# Gamebadge3_revD.net
KiCad netlist of a schematic drawn in EAGLE
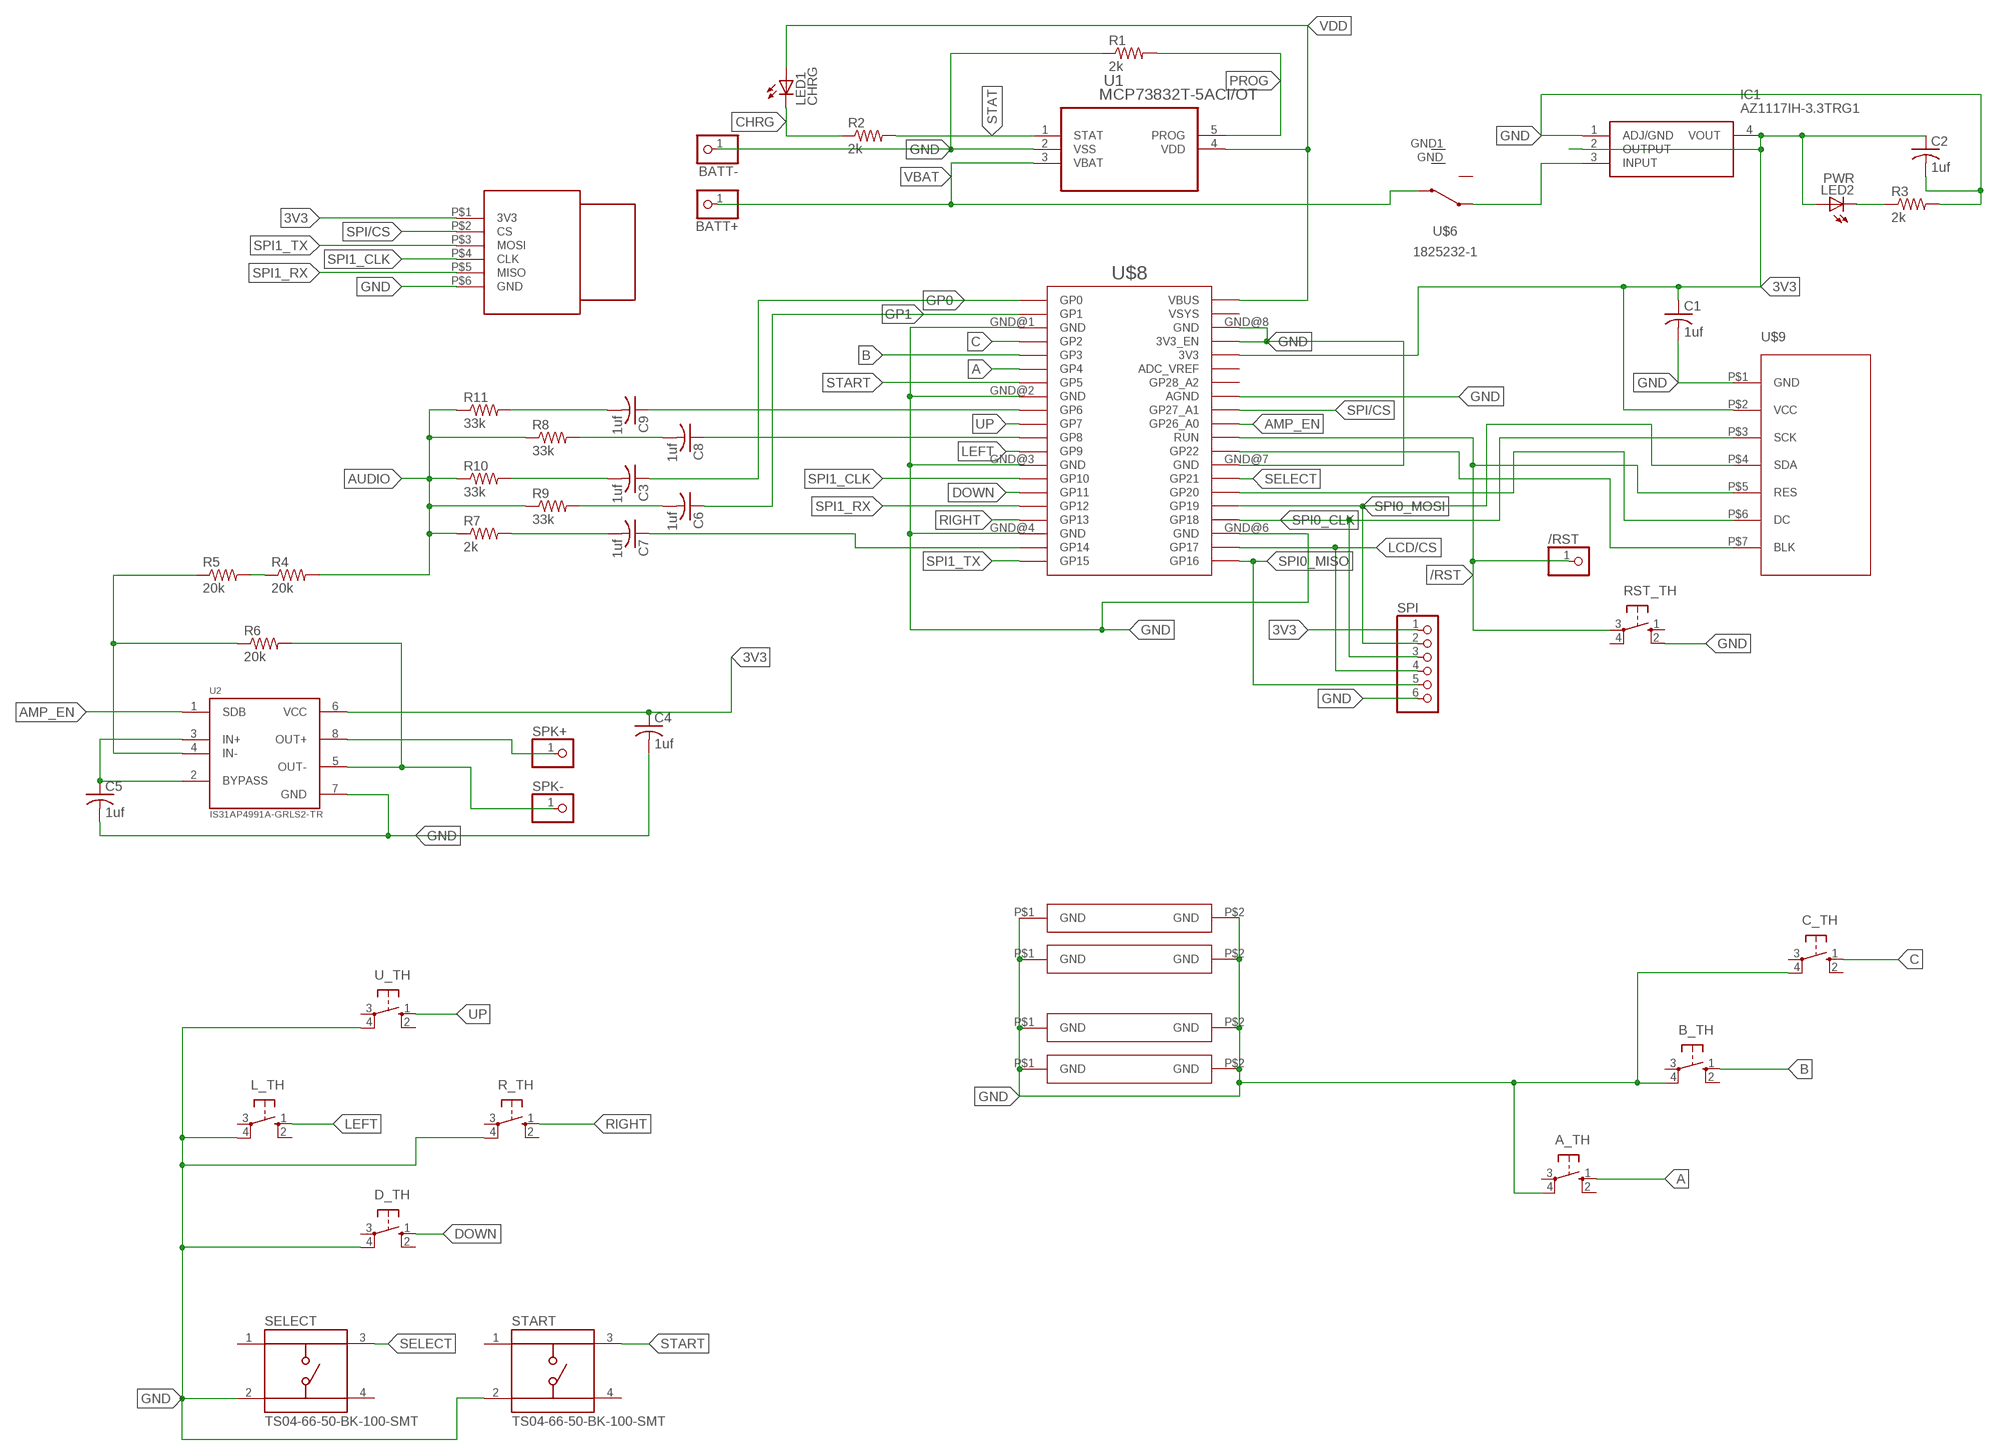
[diagram p0: schematic, sheet 1]

(export (version "E")
  (design (tool "Eeschema 10.0.6"))
  (components
    (comp (ref "/RST")
      (value "PINHD-1X1")
      (footprint "eagle-import:1X01")
      (libsource (lib "eagle-import") (part "PINHD-1X1"))
    )
    (comp (ref "A_TH")
      (value "10-XX")
      (footprint "eagle-import:B3F-10XX")
      (fields (field (name "MPN") "B3F-1000"))
      (libsource (lib "eagle-import") (part "10-XX"))
    )
    (comp (ref "BATT+")
      (value "PINHD-1X1")
      (footprint "eagle-import:1X01")
      (libsource (lib "eagle-import") (part "PINHD-1X1"))
    )
    (comp (ref "BATT-")
      (value "PINHD-1X1")
      (footprint "eagle-import:1X01")
      (libsource (lib "eagle-import") (part "PINHD-1X1"))
    )
    (comp (ref "B_TH")
      (value "10-XX")
      (footprint "eagle-import:B3F-10XX")
      (fields (field (name "MPN") "B3F-1000"))
      (libsource (lib "eagle-import") (part "10-XX"))
    )
    (comp (ref "C1")
      (value "1uf")
      (footprint "eagle-import:C0805")
      (libsource (lib "eagle-import") (part "C-USC0805"))
    )
    (comp (ref "C2")
      (value "1uf")
      (footprint "eagle-import:C0805")
      (libsource (lib "eagle-import") (part "C-USC0805"))
    )
    (comp (ref "C3")
      (value "1uf")
      (footprint "eagle-import:C0805")
      (libsource (lib "eagle-import") (part "C-USC0805"))
    )
    (comp (ref "C4")
      (value "1uf")
      (footprint "eagle-import:C0805")
      (libsource (lib "eagle-import") (part "C-USC0805"))
    )
    (comp (ref "C5")
      (value "1uf")
      (footprint "eagle-import:C0805")
      (libsource (lib "eagle-import") (part "C-USC0805"))
    )
    (comp (ref "C6")
      (value "1uf")
      (footprint "eagle-import:C0805")
      (libsource (lib "eagle-import") (part "C-USC0805"))
    )
    (comp (ref "C7")
      (value "1uf")
      (footprint "eagle-import:C0805")
      (libsource (lib "eagle-import") (part "C-USC0805"))
    )
    (comp (ref "C8")
      (value "1uf")
      (footprint "eagle-import:C0805")
      (libsource (lib "eagle-import") (part "C-USC0805"))
    )
    (comp (ref "C9")
      (value "1uf")
      (footprint "eagle-import:C0805")
      (libsource (lib "eagle-import") (part "C-USC0805"))
    )
    (comp (ref "C_TH")
      (value "10-XX")
      (footprint "eagle-import:B3F-10XX")
      (fields (field (name "MPN") "B3F-1000"))
      (libsource (lib "eagle-import") (part "10-XX"))
    )
    (comp (ref "D_TH")
      (value "10-XX")
      (footprint "eagle-import:B3F-10XX")
      (fields (field (name "MPN") "B3F-1000"))
      (libsource (lib "eagle-import") (part "10-XX"))
    )
    (comp (ref "IC1")
      (value "AZ1117IH-3.3TRG1")
      (footprint "eagle-import:SOT230P700X170-4N")
      (fields (field (name "MF") "Diodes Inc."))
      (libsource (lib "eagle-import") (part "AZ1117IH-3.3TRG1"))
    )
    (comp (ref "LED1")
      (value "CHRG")
      (footprint "eagle-import:LED3MM")
      (libsource (lib "eagle-import") (part "LED3MM"))
    )
    (comp (ref "LED2")
      (value "PWR")
      (footprint "eagle-import:LED3MM")
      (libsource (lib "eagle-import") (part "LED3MM"))
    )
    (comp (ref "L_TH")
      (value "10-XX")
      (footprint "eagle-import:B3F-10XX")
      (fields (field (name "MPN") "B3F-1000"))
      (libsource (lib "eagle-import") (part "10-XX"))
    )
    (comp (ref "R1")
      (value "2k")
      (footprint "eagle-import:R0805")
      (libsource (lib "eagle-import") (part "R-US_R0805"))
    )
    (comp (ref "R2")
      (value "2k")
      (footprint "eagle-import:R0805")
      (libsource (lib "eagle-import") (part "R-US_R0805"))
    )
    (comp (ref "R3")
      (value "2k")
      (footprint "eagle-import:R0805")
      (libsource (lib "eagle-import") (part "R-US_R0805"))
    )
    (comp (ref "R4")
      (value "20k")
      (footprint "eagle-import:R0805")
      (libsource (lib "eagle-import") (part "R-US_R0805"))
    )
    (comp (ref "R5")
      (value "20k")
      (footprint "eagle-import:R0805")
      (libsource (lib "eagle-import") (part "R-US_R0805"))
    )
    (comp (ref "R6")
      (value "20k")
      (footprint "eagle-import:R0805")
      (libsource (lib "eagle-import") (part "R-US_R0805"))
    )
    (comp (ref "R7")
      (value "2k")
      (footprint "eagle-import:R0805")
      (libsource (lib "eagle-import") (part "R-US_R0805"))
    )
    (comp (ref "R8")
      (value "33k")
      (footprint "eagle-import:R0805")
      (libsource (lib "eagle-import") (part "R-US_R0805"))
    )
    (comp (ref "R9")
      (value "33k")
      (footprint "eagle-import:R0805")
      (libsource (lib "eagle-import") (part "R-US_R0805"))
    )
    (comp (ref "R10")
      (value "33k")
      (footprint "eagle-import:R0805")
      (libsource (lib "eagle-import") (part "R-US_R0805"))
    )
    (comp (ref "R11")
      (value "33k")
      (footprint "eagle-import:R0805")
      (libsource (lib "eagle-import") (part "R-US_R0805"))
    )
    (comp (ref "RST_TH")
      (value "10-XX")
      (footprint "eagle-import:B3F-10XX")
      (fields (field (name "MPN") "B3F-1000"))
      (libsource (lib "eagle-import") (part "10-XX"))
    )
    (comp (ref "R_TH")
      (value "10-XX")
      (footprint "eagle-import:B3F-10XX")
      (fields (field (name "MPN") "B3F-1000"))
      (libsource (lib "eagle-import") (part "10-XX"))
    )
    (comp (ref "SELECT")
      (value "TS04-66-50-BK-100-SMT")
      (footprint "eagle-import:SW_TS04-66-50-BK-100-SMT")
      (fields (field (name "MF") "CUI Devices"))
      (libsource (lib "eagle-import") (part "TS04-66-50-BK-100-SMT"))
    )
    (comp (ref "SPI")
      (value "PINHD-1X6")
      (footprint "eagle-import:1X06")
      (libsource (lib "eagle-import") (part "PINHD-1X6"))
    )
    (comp (ref "SPK+")
      (value "PINHD-1X1")
      (footprint "eagle-import:1X01")
      (libsource (lib "eagle-import") (part "PINHD-1X1"))
    )
    (comp (ref "SPK-")
      (value "PINHD-1X1")
      (footprint "eagle-import:1X01")
      (libsource (lib "eagle-import") (part "PINHD-1X1"))
    )
    (comp (ref "START")
      (value "TS04-66-50-BK-100-SMT")
      (footprint "eagle-import:SW_TS04-66-50-BK-100-SMT")
      (fields (field (name "MF") "CUI Devices"))
      (libsource (lib "eagle-import") (part "TS04-66-50-BK-100-SMT"))
    )
    (comp (ref "U$1")
      (value "SD_CARD_ADAPTER")
      (footprint "eagle-import:SD_CARD")
      (libsource (lib "eagle-import") (part "SD_CARD_ADAPTER"))
    )
    (comp (ref "U$2")
      (value "GND_CLIP")
      (footprint "eagle-import:GND_CLIP")
      (libsource (lib "eagle-import") (part "GND_CLIP"))
    )
    (comp (ref "U$3")
      (value "GND_CLIP")
      (footprint "eagle-import:GND_CLIP")
      (libsource (lib "eagle-import") (part "GND_CLIP"))
    )
    (comp (ref "U$4")
      (value "GND_CLIP")
      (footprint "eagle-import:GND_CLIP")
      (libsource (lib "eagle-import") (part "GND_CLIP"))
    )
    (comp (ref "U$5")
      (value "GND_CLIP")
      (footprint "eagle-import:GND_CLIP")
      (libsource (lib "eagle-import") (part "GND_CLIP"))
    )
    (comp (ref "U$6")
      (value "1825232-1")
      (footprint "eagle-import:1825232-1")
      (fields (field (name "MF") "TE Connectivity"))
      (libsource (lib "eagle-import") (part "1825232-1"))
    )
    (comp (ref "U$8")
      (value "RPI_PICO_W")
      (footprint "eagle-import:RPI_PICO_W")
      (libsource (lib "eagle-import") (part "RPI_PICO_W"))
    )
    (comp (ref "U$9")
      (value "ST7789")
      (footprint "eagle-import:ST7789")
      (libsource (lib "eagle-import") (part "ST7789"))
    )
    (comp (ref "U1")
      (value "MCP73832T-5ACI/OT")
      (footprint "eagle-import:SOT95P300X145-5N")
      (fields (field (name "MF") "Microchip"))
      (libsource (lib "eagle-import") (part "MCP73832T-5ACI/OT"))
    )
    (comp (ref "U2")
      (value "IS31AP4991A-GRLS2-TR")
      (footprint "eagle-import:SOIC127P604X170-8N")
      (fields (field (name "MF") "Lumissil Microsystems"))
      (libsource (lib "eagle-import") (part "IS31AP4991A-GRLS2-TR"))
    )
    (comp (ref "U_TH")
      (value "10-XX")
      (footprint "eagle-import:B3F-10XX")
      (fields (field (name "MPN") "B3F-1000"))
      (libsource (lib "eagle-import") (part "10-XX"))
    )
  )
  (nets
    (net (code "1") (name "3V3") (class "Default")
      (node (ref "C1") (pin "1") (pinfunction "1_1") (pintype "passive"))
      (node (ref "C2") (pin "1") (pinfunction "1_1") (pintype "passive"))
      (node (ref "C4") (pin "1") (pinfunction "1_1") (pintype "passive"))
      (node (ref "IC1") (pin "2") (pinfunction "OUTPUT_2") (pintype "bidirectional"))
      (node (ref "IC1") (pin "4") (pinfunction "VOUT_4") (pintype "bidirectional"))
      (node (ref "LED2") (pin "A") (pinfunction "A_A") (pintype "passive"))
      (node (ref "SPI") (pin "1") (pinfunction "1_1") (pintype "passive"))
      (node (ref "U$1") (pin "P$1") (pinfunction "3V3_P$1") (pintype "bidirectional"))
      (node (ref "U$8") (pin "3V3") (pinfunction "3V3_3V3") (pintype "bidirectional"))
      (node (ref "U$9") (pin "P$2") (pinfunction "VCC_P$2") (pintype "bidirectional"))
      (node (ref "U2") (pin "6") (pinfunction "VCC_6") (pintype "power_in"))
    )
    (net (code "2") (name "A") (class "Default")
      (node (ref "A_TH") (pin "1") (pinfunction "S_1") (pintype "passive"))
      (node (ref "U$8") (pin "GP4") (pinfunction "GP4_GP4") (pintype "bidirectional"))
    )
    (net (code "3") (name "AMP_EN") (class "Default")
      (node (ref "U$8") (pin "GP26_A0") (pinfunction "GP26_A0_GP26_A0") (pintype "bidirectional"))
      (node (ref "U2") (pin "1") (pinfunction "SDB_1") (pintype "input"))
    )
    (net (code "4") (name "AUDIO") (class "Default")
      (node (ref "R10") (pin "1") (pinfunction "1_1") (pintype "passive"))
      (node (ref "R11") (pin "1") (pinfunction "1_1") (pintype "passive"))
      (node (ref "R4") (pin "2") (pinfunction "2_2") (pintype "passive"))
      (node (ref "R7") (pin "1") (pinfunction "1_1") (pintype "passive"))
      (node (ref "R8") (pin "1") (pinfunction "1_1") (pintype "passive"))
      (node (ref "R9") (pin "1") (pinfunction "1_1") (pintype "passive"))
    )
    (net (code "5") (name "B") (class "Default")
      (node (ref "B_TH") (pin "1") (pinfunction "S_1") (pintype "passive"))
      (node (ref "U$8") (pin "GP3") (pinfunction "GP3_GP3") (pintype "bidirectional"))
    )
    (net (code "6") (name "C") (class "Default")
      (node (ref "C_TH") (pin "1") (pinfunction "S_1") (pintype "passive"))
      (node (ref "U$8") (pin "GP2") (pinfunction "GP2_GP2") (pintype "bidirectional"))
    )
    (net (code "7") (name "CHRG") (class "Default")
      (node (ref "LED1") (pin "K") (pinfunction "C_K") (pintype "passive"))
      (node (ref "R2") (pin "1") (pinfunction "1_1") (pintype "passive"))
    )
    (net (code "8") (name "DOWN") (class "Default")
      (node (ref "D_TH") (pin "1") (pinfunction "S_1") (pintype "passive"))
      (node (ref "U$8") (pin "GP11") (pinfunction "GP11_GP11") (pintype "bidirectional"))
    )
    (net (code "9") (name "GND") (class "Default")
      (node (ref "A_TH") (pin "4") (pinfunction "P1_4") (pintype "passive"))
      (node (ref "BATT-") (pin "1") (pinfunction "1_1") (pintype "passive"))
      (node (ref "B_TH") (pin "4") (pinfunction "P1_4") (pintype "passive"))
      (node (ref "C1") (pin "2") (pinfunction "2_2") (pintype "passive"))
      (node (ref "C2") (pin "2") (pinfunction "2_2") (pintype "passive"))
      (node (ref "C4") (pin "2") (pinfunction "2_2") (pintype "passive"))
      (node (ref "C5") (pin "2") (pinfunction "2_2") (pintype "passive"))
      (node (ref "C_TH") (pin "4") (pinfunction "P1_4") (pintype "passive"))
      (node (ref "D_TH") (pin "4") (pinfunction "P1_4") (pintype "passive"))
      (node (ref "IC1") (pin "1") (pinfunction "ADJ/GND_1") (pintype "bidirectional"))
      (node (ref "L_TH") (pin "4") (pinfunction "P1_4") (pintype "passive"))
      (node (ref "R1") (pin "1") (pinfunction "1_1") (pintype "passive"))
      (node (ref "R3") (pin "2") (pinfunction "2_2") (pintype "passive"))
      (node (ref "RST_TH") (pin "2") (pinfunction "S1_2") (pintype "passive"))
      (node (ref "R_TH") (pin "4") (pinfunction "P1_4") (pintype "passive"))
      (node (ref "SELECT") (pin "2") (pinfunction "2_2") (pintype "passive"))
      (node (ref "SPI") (pin "6") (pinfunction "6_6") (pintype "passive"))
      (node (ref "START") (pin "2") (pinfunction "2_2") (pintype "passive"))
      (node (ref "U$1") (pin "P$6") (pinfunction "GND_P$6") (pintype "bidirectional"))
      (node (ref "U$2") (pin "P$1") (pinfunction "GND_P$1") (pintype "bidirectional"))
      (node (ref "U$2") (pin "P$2") (pinfunction "GND_P$2") (pintype "bidirectional"))
      (node (ref "U$3") (pin "P$1") (pinfunction "GND_P$1") (pintype "bidirectional"))
      (node (ref "U$3") (pin "P$2") (pinfunction "GND_P$2") (pintype "bidirectional"))
      (node (ref "U$4") (pin "P$1") (pinfunction "GND_P$1") (pintype "bidirectional"))
      (node (ref "U$4") (pin "P$2") (pinfunction "GND_P$2") (pintype "bidirectional"))
      (node (ref "U$5") (pin "P$1") (pinfunction "GND_P$1") (pintype "bidirectional"))
      (node (ref "U$5") (pin "P$2") (pinfunction "GND_P$2") (pintype "bidirectional"))
      (node (ref "U$8") (pin "3V3_EN") (pinfunction "3V3_EN_3V3_EN") (pintype "bidirectional"))
      (node (ref "U$8") (pin "AGND") (pinfunction "AGND_AGND") (pintype "bidirectional"))
      (node (ref "U$8") (pin "GND@1") (pinfunction "GND_GND@1") (pintype "bidirectional"))
      (node (ref "U$8") (pin "GND@2") (pinfunction "GND_GND@2") (pintype "bidirectional"))
      (node (ref "U$8") (pin "GND@3") (pinfunction "GND_GND@3") (pintype "bidirectional"))
      (node (ref "U$8") (pin "GND@4") (pinfunction "GND_GND@4") (pintype "bidirectional"))
      (node (ref "U$8") (pin "GND@6") (pinfunction "GND_GND@6") (pintype "bidirectional"))
      (node (ref "U$8") (pin "GND@7") (pinfunction "GND_GND@7") (pintype "bidirectional"))
      (node (ref "U$8") (pin "GND@8") (pinfunction "GND_GND@8") (pintype "bidirectional"))
      (node (ref "U$9") (pin "P$1") (pinfunction "GND_P$1") (pintype "bidirectional"))
      (node (ref "U1") (pin "2") (pinfunction "VSS_2") (pintype "passive"))
      (node (ref "U2") (pin "7") (pinfunction "GND_7") (pintype "power_in"))
      (node (ref "U_TH") (pin "4") (pinfunction "P1_4") (pintype "passive"))
    )
    (net (code "10") (name "GP0") (class "Default")
      (node (ref "C3") (pin "1") (pinfunction "1_1") (pintype "passive"))
      (node (ref "U$8") (pin "GP0") (pinfunction "GP0_GP0") (pintype "bidirectional"))
    )
    (net (code "11") (name "GP1") (class "Default")
      (node (ref "C6") (pin "1") (pinfunction "1_1") (pintype "passive"))
      (node (ref "U$8") (pin "GP1") (pinfunction "GP1_GP1") (pintype "bidirectional"))
    )
    (net (code "12") (name "LCD{slash}CS") (class "Default")
      (node (ref "SPI") (pin "4") (pinfunction "4_4") (pintype "passive"))
      (node (ref "U$8") (pin "GP17") (pinfunction "GP17_GP17") (pintype "bidirectional"))
    )
    (net (code "13") (name "LEFT") (class "Default")
      (node (ref "L_TH") (pin "1") (pinfunction "S_1") (pintype "passive"))
      (node (ref "U$8") (pin "GP9") (pinfunction "GP9_GP9") (pintype "bidirectional"))
    )
    (net (code "14") (name "Net-(C3-Pad2)") (class "Default")
      (node (ref "C3") (pin "2") (pinfunction "2_2") (pintype "passive"))
      (node (ref "R10") (pin "2") (pinfunction "2_2") (pintype "passive"))
    )
    (net (code "15") (name "Net-(C6-Pad2)") (class "Default")
      (node (ref "C6") (pin "2") (pinfunction "2_2") (pintype "passive"))
      (node (ref "R9") (pin "2") (pinfunction "2_2") (pintype "passive"))
    )
    (net (code "16") (name "Net-(C7-Pad1)") (class "Default")
      (node (ref "C7") (pin "1") (pinfunction "1_1") (pintype "passive"))
      (node (ref "U$8") (pin "GP14") (pinfunction "GP14_GP14") (pintype "bidirectional"))
    )
    (net (code "17") (name "Net-(C7-Pad2)") (class "Default")
      (node (ref "C7") (pin "2") (pinfunction "2_2") (pintype "passive"))
      (node (ref "R7") (pin "2") (pinfunction "2_2") (pintype "passive"))
    )
    (net (code "18") (name "Net-(C8-Pad1)") (class "Default")
      (node (ref "C8") (pin "1") (pinfunction "1_1") (pintype "passive"))
      (node (ref "U$8") (pin "GP8") (pinfunction "GP8_GP8") (pintype "bidirectional"))
    )
    (net (code "19") (name "Net-(C8-Pad2)") (class "Default")
      (node (ref "C8") (pin "2") (pinfunction "2_2") (pintype "passive"))
      (node (ref "R8") (pin "2") (pinfunction "2_2") (pintype "passive"))
    )
    (net (code "20") (name "Net-(C9-Pad1)") (class "Default")
      (node (ref "C9") (pin "1") (pinfunction "1_1") (pintype "passive"))
      (node (ref "U$8") (pin "GP6") (pinfunction "GP6_GP6") (pintype "bidirectional"))
    )
    (net (code "21") (name "Net-(C9-Pad2)") (class "Default")
      (node (ref "C9") (pin "2") (pinfunction "2_2") (pintype "passive"))
      (node (ref "R11") (pin "2") (pinfunction "2_2") (pintype "passive"))
    )
    (net (code "22") (name "Net-(IC1-INPUT)") (class "Default")
      (node (ref "IC1") (pin "3") (pinfunction "INPUT_3") (pintype "bidirectional"))
      (node (ref "U$6") (pin "3") (pinfunction "3_3") (pintype "passive"))
    )
    (net (code "23") (name "Net-(LED2-C)") (class "Default")
      (node (ref "LED2") (pin "K") (pinfunction "C_K") (pintype "passive"))
      (node (ref "R3") (pin "1") (pinfunction "1_1") (pintype "passive"))
    )
    (net (code "24") (name "Net-(R4-Pad1)") (class "Default")
      (node (ref "R4") (pin "1") (pinfunction "1_1") (pintype "passive"))
      (node (ref "R5") (pin "2") (pinfunction "2_2") (pintype "passive"))
    )
    (net (code "25") (name "Net-(U$9-BLK)") (class "Default")
      (node (ref "U$8") (pin "GP22") (pinfunction "GP22_GP22") (pintype "bidirectional"))
      (node (ref "U$9") (pin "P$7") (pinfunction "BLK_P$7") (pintype "bidirectional"))
    )
    (net (code "26") (name "Net-(U$9-DC)") (class "Default")
      (node (ref "U$8") (pin "GP20") (pinfunction "GP20_GP20") (pintype "bidirectional"))
      (node (ref "U$9") (pin "P$6") (pinfunction "DC_P$6") (pintype "bidirectional"))
    )
    (net (code "27") (name "Net-(U2-BYPASS)") (class "Default")
      (node (ref "C5") (pin "1") (pinfunction "1_1") (pintype "passive"))
      (node (ref "U2") (pin "2") (pinfunction "BYPASS_2") (pintype "passive"))
      (node (ref "U2") (pin "3") (pinfunction "IN+_3") (pintype "input"))
    )
    (net (code "28") (name "Net-(U2-IN-)") (class "Default")
      (node (ref "R5") (pin "1") (pinfunction "1_1") (pintype "passive"))
      (node (ref "R6") (pin "1") (pinfunction "1_1") (pintype "passive"))
      (node (ref "U2") (pin "4") (pinfunction "IN-_4") (pintype "input"))
    )
    (net (code "29") (name "Net-(U2-OUT+)") (class "Default")
      (node (ref "SPK+") (pin "1") (pinfunction "1_1") (pintype "passive"))
      (node (ref "U2") (pin "8") (pinfunction "OUT+_8") (pintype "output"))
    )
    (net (code "30") (name "Net-(U2-OUT-)") (class "Default")
      (node (ref "R6") (pin "2") (pinfunction "2_2") (pintype "passive"))
      (node (ref "SPK-") (pin "1") (pinfunction "1_1") (pintype "passive"))
      (node (ref "U2") (pin "5") (pinfunction "OUT-_5") (pintype "output"))
    )
    (net (code "31") (name "PROG") (class "Default")
      (node (ref "R1") (pin "2") (pinfunction "2_2") (pintype "passive"))
      (node (ref "U1") (pin "5") (pinfunction "PROG_5") (pintype "input"))
    )
    (net (code "32") (name "RIGHT") (class "Default")
      (node (ref "R_TH") (pin "1") (pinfunction "S_1") (pintype "passive"))
      (node (ref "U$8") (pin "GP13") (pinfunction "GP13_GP13") (pintype "bidirectional"))
    )
    (net (code "33") (name "SELECT") (class "Default")
      (node (ref "SELECT") (pin "3") (pinfunction "3_3") (pintype "passive"))
      (node (ref "U$8") (pin "GP21") (pinfunction "GP21_GP21") (pintype "bidirectional"))
    )
    (net (code "34") (name "SPI0_CLK") (class "Default")
      (node (ref "SPI") (pin "3") (pinfunction "3_3") (pintype "passive"))
      (node (ref "U$8") (pin "GP18") (pinfunction "GP18_GP18") (pintype "bidirectional"))
      (node (ref "U$9") (pin "P$3") (pinfunction "SCK_P$3") (pintype "bidirectional"))
    )
    (net (code "35") (name "SPI0_MISO") (class "Default")
      (node (ref "SPI") (pin "5") (pinfunction "5_5") (pintype "passive"))
      (node (ref "U$8") (pin "GP16") (pinfunction "GP16_GP16") (pintype "bidirectional"))
    )
    (net (code "36") (name "SPI0_MOSI") (class "Default")
      (node (ref "SPI") (pin "2") (pinfunction "2_2") (pintype "passive"))
      (node (ref "U$8") (pin "GP19") (pinfunction "GP19_GP19") (pintype "bidirectional"))
      (node (ref "U$9") (pin "P$4") (pinfunction "SDA_P$4") (pintype "bidirectional"))
    )
    (net (code "37") (name "SPI1_CLK") (class "Default")
      (node (ref "U$1") (pin "P$4") (pinfunction "CLK_P$4") (pintype "bidirectional"))
      (node (ref "U$8") (pin "GP10") (pinfunction "GP10_GP10") (pintype "bidirectional"))
    )
    (net (code "38") (name "SPI1_RX") (class "Default")
      (node (ref "U$1") (pin "P$5") (pinfunction "MISO_P$5") (pintype "bidirectional"))
      (node (ref "U$8") (pin "GP12") (pinfunction "GP12_GP12") (pintype "bidirectional"))
    )
    (net (code "39") (name "SPI1_TX") (class "Default")
      (node (ref "U$1") (pin "P$3") (pinfunction "MOSI_P$3") (pintype "bidirectional"))
      (node (ref "U$8") (pin "GP15") (pinfunction "GP15_GP15") (pintype "bidirectional"))
    )
    (net (code "40") (name "SPI{slash}CS") (class "Default")
      (node (ref "U$1") (pin "P$2") (pinfunction "CS_P$2") (pintype "bidirectional"))
      (node (ref "U$8") (pin "GP27_A1") (pinfunction "GP27_A1_GP27_A1") (pintype "bidirectional"))
    )
    (net (code "41") (name "START") (class "Default")
      (node (ref "START") (pin "3") (pinfunction "3_3") (pintype "passive"))
      (node (ref "U$8") (pin "GP5") (pinfunction "GP5_GP5") (pintype "bidirectional"))
    )
    (net (code "42") (name "STAT") (class "Default")
      (node (ref "R2") (pin "2") (pinfunction "2_2") (pintype "passive"))
      (node (ref "U1") (pin "1") (pinfunction "STAT_1") (pintype "input"))
    )
    (net (code "43") (name "UP") (class "Default")
      (node (ref "U$8") (pin "GP7") (pinfunction "GP7_GP7") (pintype "bidirectional"))
      (node (ref "U_TH") (pin "1") (pinfunction "S_1") (pintype "passive"))
    )
    (net (code "44") (name "VBAT") (class "Default")
      (node (ref "BATT+") (pin "1") (pinfunction "1_1") (pintype "passive"))
      (node (ref "U$6") (pin "2") (pinfunction "2_2") (pintype "passive"))
      (node (ref "U1") (pin "3") (pinfunction "VBAT_3") (pintype "input"))
    )
    (net (code "45") (name "VDD") (class "Default")
      (node (ref "LED1") (pin "A") (pinfunction "A_A") (pintype "passive"))
      (node (ref "U$8") (pin "VBUS") (pinfunction "VBUS_VBUS") (pintype "bidirectional"))
      (node (ref "U1") (pin "4") (pinfunction "VDD_4") (pintype "power_in"))
    )
    (net (code "46") (name "unconnected-(A_TH-P-Pad3)") (class "Default")
      (node (ref "A_TH") (pin "3") (pinfunction "P_3") (pintype "passive"))
    )
    (net (code "47") (name "unconnected-(A_TH-S1-Pad2)") (class "Default")
      (node (ref "A_TH") (pin "2") (pinfunction "S1_2") (pintype "passive"))
    )
    (net (code "48") (name "unconnected-(B_TH-P-Pad3)") (class "Default")
      (node (ref "B_TH") (pin "3") (pinfunction "P_3") (pintype "passive"))
    )
    (net (code "49") (name "unconnected-(B_TH-S1-Pad2)") (class "Default")
      (node (ref "B_TH") (pin "2") (pinfunction "S1_2") (pintype "passive"))
    )
    (net (code "50") (name "unconnected-(C_TH-P-Pad3)") (class "Default")
      (node (ref "C_TH") (pin "3") (pinfunction "P_3") (pintype "passive"))
    )
    (net (code "51") (name "unconnected-(C_TH-S1-Pad2)") (class "Default")
      (node (ref "C_TH") (pin "2") (pinfunction "S1_2") (pintype "passive"))
    )
    (net (code "52") (name "unconnected-(D_TH-P-Pad3)") (class "Default")
      (node (ref "D_TH") (pin "3") (pinfunction "P_3") (pintype "passive"))
    )
    (net (code "53") (name "unconnected-(D_TH-S1-Pad2)") (class "Default")
      (node (ref "D_TH") (pin "2") (pinfunction "S1_2") (pintype "passive"))
    )
    (net (code "54") (name "unconnected-(L_TH-P-Pad3)") (class "Default")
      (node (ref "L_TH") (pin "3") (pinfunction "P_3") (pintype "passive"))
    )
    (net (code "55") (name "unconnected-(L_TH-S1-Pad2)") (class "Default")
      (node (ref "L_TH") (pin "2") (pinfunction "S1_2") (pintype "passive"))
    )
    (net (code "56") (name "unconnected-(RST_TH-P1-Pad4)") (class "Default")
      (node (ref "RST_TH") (pin "4") (pinfunction "P1_4") (pintype "passive"))
    )
    (net (code "57") (name "unconnected-(RST_TH-S-Pad1)") (class "Default")
      (node (ref "RST_TH") (pin "1") (pinfunction "S_1") (pintype "passive"))
    )
    (net (code "58") (name "unconnected-(R_TH-P-Pad3)") (class "Default")
      (node (ref "R_TH") (pin "3") (pinfunction "P_3") (pintype "passive"))
    )
    (net (code "59") (name "unconnected-(R_TH-S1-Pad2)") (class "Default")
      (node (ref "R_TH") (pin "2") (pinfunction "S1_2") (pintype "passive"))
    )
    (net (code "60") (name "unconnected-(SELECT-Pad1)") (class "Default")
      (node (ref "SELECT") (pin "1") (pinfunction "1_1") (pintype "passive"))
    )
    (net (code "61") (name "unconnected-(SELECT-Pad4)") (class "Default")
      (node (ref "SELECT") (pin "4") (pinfunction "4_4") (pintype "passive"))
    )
    (net (code "62") (name "unconnected-(START-Pad1)") (class "Default")
      (node (ref "START") (pin "1") (pinfunction "1_1") (pintype "passive"))
    )
    (net (code "63") (name "unconnected-(START-Pad4)") (class "Default")
      (node (ref "START") (pin "4") (pinfunction "4_4") (pintype "passive"))
    )
    (net (code "64") (name "unconnected-(U$6-Pad1)") (class "Default")
      (node (ref "U$6") (pin "1") (pinfunction "1_1") (pintype "passive"))
    )
    (net (code "65") (name "unconnected-(U$6-PadGND)") (class "Default")
      (node (ref "U$6") (pin "GND") (pinfunction "GND_GND") (pintype "passive"))
    )
    (net (code "66") (name "unconnected-(U$6-PadGND1)") (class "Default")
      (node (ref "U$6") (pin "GND1") (pinfunction "GND1_GND1") (pintype "passive"))
    )
    (net (code "67") (name "unconnected-(U$8-PadADC_VREF)") (class "Default")
      (node (ref "U$8") (pin "ADC_VREF") (pinfunction "ADC_VREF_ADC_VREF") (pintype "bidirectional"))
    )
    (net (code "68") (name "unconnected-(U$8-PadGP28_A2)") (class "Default")
      (node (ref "U$8") (pin "GP28_A2") (pinfunction "GP28_A2_GP28_A2") (pintype "bidirectional"))
    )
    (net (code "69") (name "unconnected-(U$8-PadVSYS)") (class "Default")
      (node (ref "U$8") (pin "VSYS") (pinfunction "VSYS_VSYS") (pintype "bidirectional"))
    )
    (net (code "70") (name "unconnected-(U_TH-P-Pad3)") (class "Default")
      (node (ref "U_TH") (pin "3") (pinfunction "P_3") (pintype "passive"))
    )
    (net (code "71") (name "unconnected-(U_TH-S1-Pad2)") (class "Default")
      (node (ref "U_TH") (pin "2") (pinfunction "S1_2") (pintype "passive"))
    )
    (net (code "72") (name "{slash}RST") (class "Default")
      (node (ref "/RST") (pin "1") (pinfunction "1_1") (pintype "passive"))
      (node (ref "RST_TH") (pin "3") (pinfunction "P_3") (pintype "passive"))
      (node (ref "U$8") (pin "RUN") (pinfunction "RUN_RUN") (pintype "bidirectional"))
      (node (ref "U$9") (pin "P$5") (pinfunction "RES_P$5") (pintype "bidirectional"))
    )
  )
)
